# 15_eMMC_FLASH.net
KiCad netlist of a schematic drawn in Altium Designer
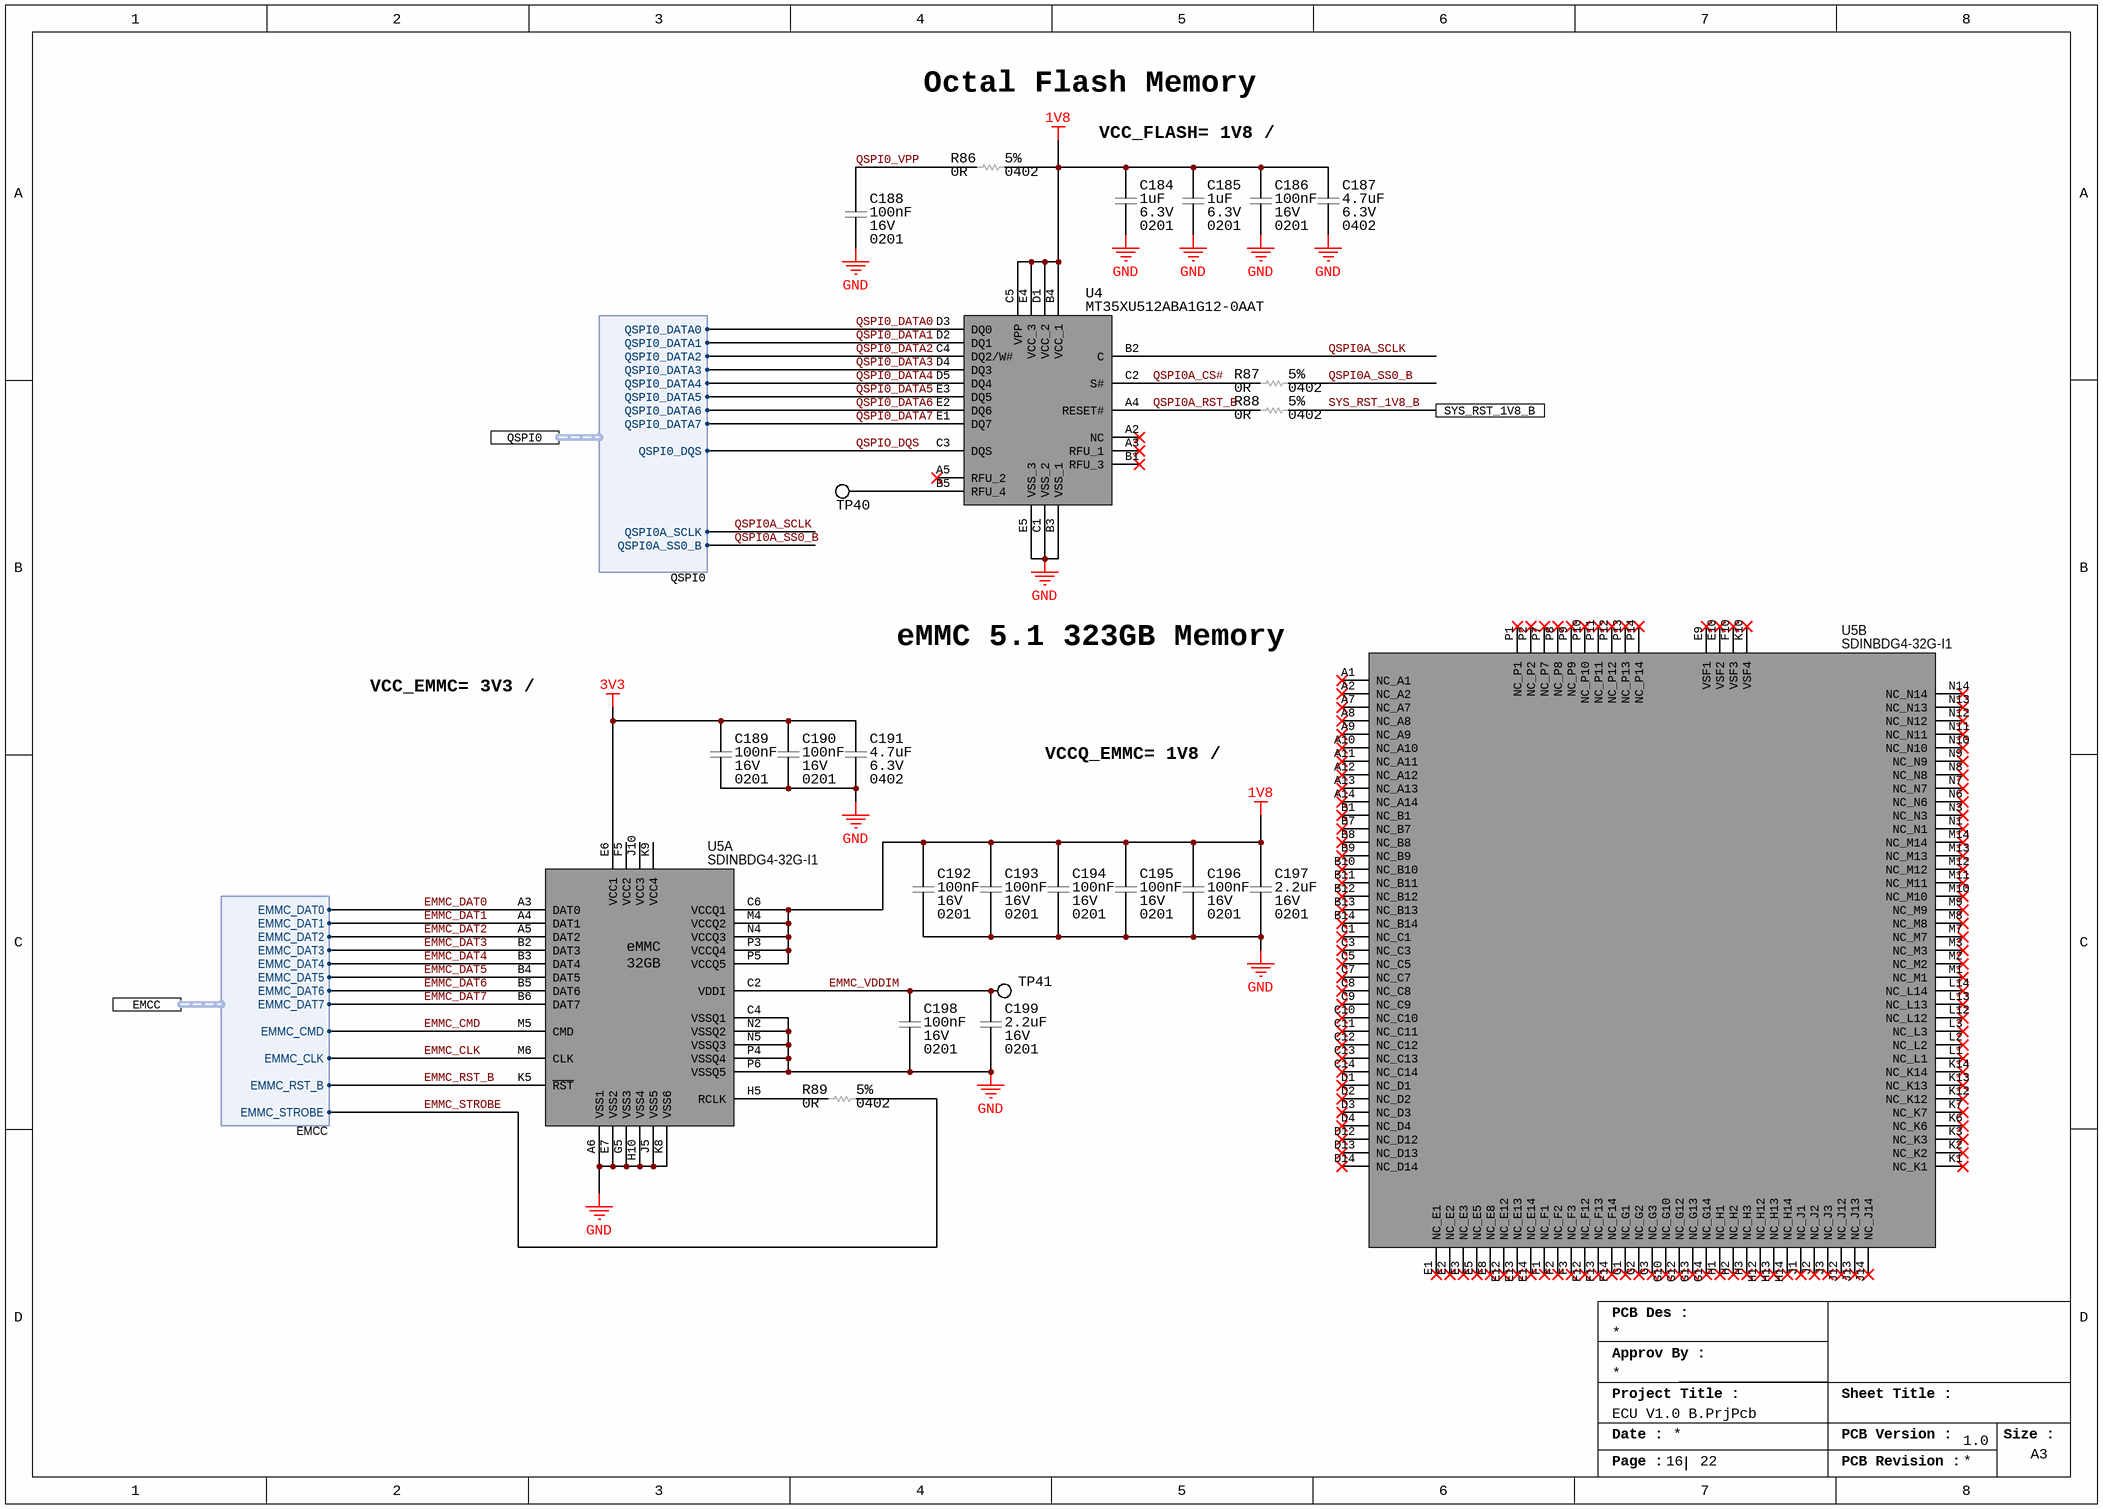
[diagram p0: 15_eMMC_FLASH.SchDoc]

(export (version "E")
  (design (tool "Eeschema 10.0.6"))
  (components
    (comp (ref "C184")
      (value "02016D105MAT2A")
      (footprint "CAP_0201_CAPC0603X03N")
      (description "0201 1 uF 6.3 V ±20 % Tolerance X5R Surface Mount Multilayer Ceramic Capacitor")
      (fields
        (field (name "MANUFACTURER") "Kyocera AVX")
        (field (name "TOLERANCE") "20%")
        (field (name "VOLTAGE RATING (DC)") "6.3V")
        (field (name "CAPACITANCE") "1uF")
        (field (name "CASE/PACKAGE") "0201")
      )
      (libsource (lib "Electronic Devices_LIB") (part "CAP_1UF_6.3V_X5R_0201"))
    )
    (comp (ref "C185")
      (value "02016D105MAT2A")
      (footprint "CAP_0201_CAPC0603X03N")
      (description "0201 1 uF 6.3 V ±20 % Tolerance X5R Surface Mount Multilayer Ceramic Capacitor")
      (fields
        (field (name "MANUFACTURER") "Kyocera AVX")
        (field (name "TOLERANCE") "20%")
        (field (name "VOLTAGE RATING (DC)") "6.3V")
        (field (name "CAPACITANCE") "1uF")
        (field (name "CASE/PACKAGE") "0201")
      )
      (libsource (lib "Electronic Devices_LIB") (part "CAP_1UF_6.3V_X5R_0201"))
    )
    (comp (ref "C186")
      (value "GRM033C71C104KE14D")
      (footprint "CAP_0201_CAPC0603X03N")
      (description "Multilayer Ceramic Capacitor, 0.1 uF, 16 V, ± 10%, X7S, 0201 [0603 Metric]")
      (fields
        (field (name "MANUFACTURER") "Murata")
        (field (name "TOLERANCE") "10%")
        (field (name "VOLTAGE RATING") "16V")
        (field (name "CAPACITANCE") "100nF")
        (field (name "CASE/PACKAGE") "0201")
      )
      (libsource (lib "Electronic Devices_LIB") (part "CAP_100nF_16V_X7S_0201"))
    )
    (comp (ref "C187")
      (value "C1005X5R0J475M050BC")
      (footprint "CAP_0402_CAPC1005X05N")
      (description "Multilayer Ceramic Capacitor, 4.7 uF, 6.3 V, ± 20%, X5R, 0402 [1005 Metric]")
      (fields
        (field (name "MANUFACTURER") "TDK")
        (field (name "TOLERANCE") "20%")
        (field (name "CAPACITANCE") "4.7uF")
        (field (name "VOLTAGE RATING") "6.3V")
        (field (name "CASE/PACKAGE") "0402")
      )
      (libsource (lib "Electronic Devices_LIB") (part "CAP_4.7UF_6.3V_X5R_0402"))
    )
    (comp (ref "C188")
      (value "GRM033C71C104KE14D")
      (footprint "CAP_0201_CAPC0603X03N")
      (description "Multilayer Ceramic Capacitor, 0.1 uF, 16 V, ± 10%, X7S, 0201 [0603 Metric]")
      (fields
        (field (name "MANUFACTURER") "Murata")
        (field (name "TOLERANCE") "10%")
        (field (name "VOLTAGE RATING") "16V")
        (field (name "CAPACITANCE") "100nF")
        (field (name "CASE/PACKAGE") "0201")
      )
      (libsource (lib "Electronic Devices_LIB") (part "CAP_100nF_16V_X7S_0201"))
    )
    (comp (ref "C189")
      (value "GRM033C71C104KE14D")
      (footprint "CAP_0201_CAPC0603X03N")
      (description "Multilayer Ceramic Capacitor, 0.1 uF, 16 V, ± 10%, X7S, 0201 [0603 Metric]")
      (fields
        (field (name "MANUFACTURER") "Murata")
        (field (name "TOLERANCE") "10%")
        (field (name "VOLTAGE RATING") "16V")
        (field (name "CAPACITANCE") "100nF")
        (field (name "CASE/PACKAGE") "0201")
      )
      (libsource (lib "Electronic Devices_LIB") (part "CAP_100nF_16V_X7S_0201"))
    )
    (comp (ref "C190")
      (value "GRM033C71C104KE14D")
      (footprint "CAP_0201_CAPC0603X03N")
      (description "Multilayer Ceramic Capacitor, 0.1 uF, 16 V, ± 10%, X7S, 0201 [0603 Metric]")
      (fields
        (field (name "MANUFACTURER") "Murata")
        (field (name "TOLERANCE") "10%")
        (field (name "VOLTAGE RATING") "16V")
        (field (name "CAPACITANCE") "100nF")
        (field (name "CASE/PACKAGE") "0201")
      )
      (libsource (lib "Electronic Devices_LIB") (part "CAP_100nF_16V_X7S_0201"))
    )
    (comp (ref "C191")
      (value "C1005X5R0J475M050BC")
      (footprint "CAP_0402_CAPC1005X05N")
      (description "Multilayer Ceramic Capacitor, 4.7 uF, 6.3 V, ± 20%, X5R, 0402 [1005 Metric]")
      (fields
        (field (name "MANUFACTURER") "TDK")
        (field (name "TOLERANCE") "20%")
        (field (name "CAPACITANCE") "4.7uF")
        (field (name "VOLTAGE RATING") "6.3V")
        (field (name "CASE/PACKAGE") "0402")
      )
      (libsource (lib "Electronic Devices_LIB") (part "CAP_4.7UF_6.3V_X5R_0402"))
    )
    (comp (ref "C192")
      (value "GRM033C71C104KE14D")
      (footprint "CAP_0201_CAPC0603X03N")
      (description "Multilayer Ceramic Capacitor, 0.1 uF, 16 V, ± 10%, X7S, 0201 [0603 Metric]")
      (fields
        (field (name "MANUFACTURER") "Murata")
        (field (name "TOLERANCE") "10%")
        (field (name "VOLTAGE RATING") "16V")
        (field (name "CAPACITANCE") "100nF")
        (field (name "CASE/PACKAGE") "0201")
      )
      (libsource (lib "Electronic Devices_LIB") (part "CAP_100nF_16V_X7S_0201"))
    )
    (comp (ref "C193")
      (value "GRM033C71C104KE14D")
      (footprint "CAP_0201_CAPC0603X03N")
      (description "Multilayer Ceramic Capacitor, 0.1 uF, 16 V, ± 10%, X7S, 0201 [0603 Metric]")
      (fields
        (field (name "MANUFACTURER") "Murata")
        (field (name "TOLERANCE") "10%")
        (field (name "VOLTAGE RATING") "16V")
        (field (name "CAPACITANCE") "100nF")
        (field (name "CASE/PACKAGE") "0201")
      )
      (libsource (lib "Electronic Devices_LIB") (part "CAP_100nF_16V_X7S_0201"))
    )
    (comp (ref "C194")
      (value "GRM033C71C104KE14D")
      (footprint "CAP_0201_CAPC0603X03N")
      (description "Multilayer Ceramic Capacitor, 0.1 uF, 16 V, ± 10%, X7S, 0201 [0603 Metric]")
      (fields
        (field (name "MANUFACTURER") "Murata")
        (field (name "TOLERANCE") "10%")
        (field (name "VOLTAGE RATING") "16V")
        (field (name "CAPACITANCE") "100nF")
        (field (name "CASE/PACKAGE") "0201")
      )
      (libsource (lib "Electronic Devices_LIB") (part "CAP_100nF_16V_X7S_0201"))
    )
    (comp (ref "C195")
      (value "GRM033C71C104KE14D")
      (footprint "CAP_0201_CAPC0603X03N")
      (description "Multilayer Ceramic Capacitor, 0.1 uF, 16 V, ± 10%, X7S, 0201 [0603 Metric]")
      (fields
        (field (name "MANUFACTURER") "Murata")
        (field (name "TOLERANCE") "10%")
        (field (name "VOLTAGE RATING") "16V")
        (field (name "CAPACITANCE") "100nF")
        (field (name "CASE/PACKAGE") "0201")
      )
      (libsource (lib "Electronic Devices_LIB") (part "CAP_100nF_16V_X7S_0201"))
    )
    (comp (ref "C196")
      (value "GRM033C71C104KE14D")
      (footprint "CAP_0201_CAPC0603X03N")
      (description "Multilayer Ceramic Capacitor, 0.1 uF, 16 V, ± 10%, X7S, 0201 [0603 Metric]")
      (fields
        (field (name "MANUFACTURER") "Murata")
        (field (name "TOLERANCE") "10%")
        (field (name "VOLTAGE RATING") "16V")
        (field (name "CAPACITANCE") "100nF")
        (field (name "CASE/PACKAGE") "0201")
      )
      (libsource (lib "Electronic Devices_LIB") (part "CAP_100nF_16V_X7S_0201"))
    )
    (comp (ref "C197")
      (value "GRM035R61C225ME01D")
      (footprint "CAP_0201_CAPC0603X03N")
      (description "General Up to 85C Reflow soldering")
      (fields
        (field (name "MANUFACTURER") "Murata")
        (field (name "TOLERANCE") "20%")
        (field (name "CAPACITANCE") "2.2uF")
        (field (name "VOLTAGE RATING") "16V")
        (field (name "CASE/PACKAGE") "0201")
      )
      (libsource (lib "Electronic Devices_LIB") (part "CAP_2.2uF_16V_X5R_0201"))
    )
    (comp (ref "C198")
      (value "GRM033C71C104KE14D")
      (footprint "CAP_0201_CAPC0603X03N")
      (description "Multilayer Ceramic Capacitor, 0.1 uF, 16 V, ± 10%, X7S, 0201 [0603 Metric]")
      (fields
        (field (name "MANUFACTURER") "Murata")
        (field (name "TOLERANCE") "10%")
        (field (name "VOLTAGE RATING") "16V")
        (field (name "CAPACITANCE") "100nF")
        (field (name "CASE/PACKAGE") "0201")
      )
      (libsource (lib "Electronic Devices_LIB") (part "CAP_100nF_16V_X7S_0201"))
    )
    (comp (ref "C199")
      (value "GRM035R61C225ME01D")
      (footprint "CAP_0201_CAPC0603X03N")
      (description "General Up to 85C Reflow soldering")
      (fields
        (field (name "MANUFACTURER") "Murata")
        (field (name "TOLERANCE") "20%")
        (field (name "CAPACITANCE") "2.2uF")
        (field (name "VOLTAGE RATING") "16V")
        (field (name "CASE/PACKAGE") "0201")
      )
      (libsource (lib "Electronic Devices_LIB") (part "CAP_2.2uF_16V_X5R_0201"))
    )
    (comp (ref "R86")
      (value "ERJ-2GE0R00X")
      (footprint "RES_0402_RESC1005X04N")
      (description "SMD Chip Resistor, Jumper, 0 ohm, 100 mW, 0402 [1005 Metric], Thick Film, General Purpose")
      (fields
        (field (name "MANUFACTURER") "Panasonic")
        (field (name "CASE CODE (IMPERIAL)") "0402")
        (field (name "TOLERANCE") "5%")
        (field (name "RESISTANCE") "0R")
      )
      (libsource (lib "Electronic Devices_LIB") (part "RES_0R_5%_100mW_0402"))
    )
    (comp (ref "R87")
      (value "ERJ-2GE0R00X")
      (footprint "RES_0402_RESC1005X04N")
      (description "SMD Chip Resistor, Jumper, 0 ohm, 100 mW, 0402 [1005 Metric], Thick Film, General Purpose")
      (fields
        (field (name "MANUFACTURER") "Panasonic")
        (field (name "CASE CODE (IMPERIAL)") "0402")
        (field (name "TOLERANCE") "5%")
        (field (name "RESISTANCE") "0R")
      )
      (libsource (lib "Electronic Devices_LIB") (part "RES_0R_5%_100mW_0402"))
    )
    (comp (ref "R88")
      (value "ERJ-2GE0R00X")
      (footprint "RES_0402_RESC1005X04N")
      (description "SMD Chip Resistor, Jumper, 0 ohm, 100 mW, 0402 [1005 Metric], Thick Film, General Purpose")
      (fields
        (field (name "MANUFACTURER") "Panasonic")
        (field (name "CASE CODE (IMPERIAL)") "0402")
        (field (name "TOLERANCE") "5%")
        (field (name "RESISTANCE") "0R")
      )
      (libsource (lib "Electronic Devices_LIB") (part "RES_0R_5%_100mW_0402"))
    )
    (comp (ref "R89")
      (value "ERJ-2GE0R00X")
      (footprint "RES_0402_RESC1005X04N")
      (description "SMD Chip Resistor, Jumper, 0 ohm, 100 mW, 0402 [1005 Metric], Thick Film, General Purpose")
      (fields
        (field (name "MANUFACTURER") "Panasonic")
        (field (name "CASE CODE (IMPERIAL)") "0402")
        (field (name "TOLERANCE") "5%")
        (field (name "RESISTANCE") "0R")
      )
      (libsource (lib "Electronic Devices_LIB") (part "RES_0R_5%_100mW_0402"))
    )
    (comp (ref "TP40")
      (value "NO COMPONENT")
      (footprint "TP_PAD_0.5MM_SMD_ROUND")
      (description "Test Point, SMD pad, round, 1.5mm, 1.6mm, 3mm diameter")
      (libsource (lib "Electronic Devices_LIB") (part "TP_PAD_SMD_SMALL"))
    )
    (comp (ref "TP41")
      (value "NO COMPONENT")
      (footprint "TP_PAD_0.5MM_SMD_ROUND")
      (description "Test Point, SMD pad, round, 1.5mm, 1.6mm, 3mm diameter")
      (libsource (lib "Electronic Devices_LIB") (part "TP_PAD_SMD_SMALL"))
    )
    (comp (ref "U4")
      (value "MT35XU512ABA1G12-0AAT")
      (footprint "BGA24C100P5X5_600X800X120")
      (description "NOR Flash, NOR Flash for Automotive, 512Mb, 1.7V-2.0V, 200 MHz, 24-ball T-PBGA, RoHS")
      (fields (field (name "MANUFACTURER") "Micron Technology"))
      (libsource (lib "Electronic Devices_LIB") (part "IC_MEMORY_FLASH_512Mb_MT35XU512ABA1G12-0AAT"))
    )
    (comp (ref "U5")
      (value "SDINBDG4-32G-I1")
      (footprint "IC_MEMORY_eMMC")
      (description "Inand 7250 32GB Industrial Wide Temp -25C+85C EMMC5.1 HS400")
      (fields (field (name "MANUFACTURER") "SanDisk"))
      (libsource (lib "Electronic Devices_LIB") (part "IC_MEMORY_eMMC_SDINBDG4-32G-I1"))
    )
  )
  (nets
    (net (code "3") (name "/EMMC_CLK") (class "Default")
      (node (ref "U5") (pin "M6") (pinfunction "CLK_M6") (pintype "passive"))
    )
    (net (code "4") (name "/EMMC_CMD") (class "Default")
      (node (ref "U5") (pin "M5") (pinfunction "CMD_M5") (pintype "passive"))
    )
    (net (code "5") (name "/EMMC_DAT0") (class "Default")
      (node (ref "U5") (pin "A3") (pinfunction "DAT0_A3") (pintype "passive"))
    )
    (net (code "6") (name "/EMMC_DAT1") (class "Default")
      (node (ref "U5") (pin "A4") (pinfunction "DAT1_A4") (pintype "passive"))
    )
    (net (code "7") (name "/EMMC_DAT2") (class "Default")
      (node (ref "U5") (pin "A5") (pinfunction "DAT2_A5") (pintype "passive"))
    )
    (net (code "8") (name "/EMMC_DAT3") (class "Default")
      (node (ref "U5") (pin "B2") (pinfunction "DAT3_B2") (pintype "passive"))
    )
    (net (code "9") (name "/EMMC_DAT4") (class "Default")
      (node (ref "U5") (pin "B3") (pinfunction "DAT4_B3") (pintype "passive"))
    )
    (net (code "10") (name "/EMMC_DAT5") (class "Default")
      (node (ref "U5") (pin "B4") (pinfunction "DAT5_B4") (pintype "passive"))
    )
    (net (code "11") (name "/EMMC_DAT6") (class "Default")
      (node (ref "U5") (pin "B5") (pinfunction "DAT6_B5") (pintype "passive"))
    )
    (net (code "12") (name "/EMMC_DAT7") (class "Default")
      (node (ref "U5") (pin "B6") (pinfunction "DAT7_B6") (pintype "passive"))
    )
    (net (code "13") (name "/EMMC_RST_B") (class "Default")
      (node (ref "U5") (pin "K5") (pinfunction "~{RST}_K5") (pintype "passive"))
    )
    (net (code "14") (name "/EMMC_STROBE") (class "Default")
      (node (ref "R89") (pin "2") (pinfunction "2_2") (pintype "passive"))
    )
    (net (code "15") (name "/EMMC_VDDIM") (class "Default")
      (node (ref "C198") (pin "2") (pinfunction "2_2") (pintype "passive"))
      (node (ref "C199") (pin "2") (pinfunction "2_2") (pintype "passive"))
      (node (ref "TP41") (pin "1") (pinfunction "1_1") (pintype "passive"))
      (node (ref "U5") (pin "C2") (pinfunction "VDDI_C2") (pintype "power_in"))
    )
    (net (code "16") (name "/QSPI0A_CS#") (class "Default")
      (node (ref "R87") (pin "1") (pinfunction "1_1") (pintype "passive"))
      (node (ref "U4") (pin "C2") (pinfunction "S#_C2") (pintype "passive"))
    )
    (net (code "17") (name "/QSPI0A_RST_B") (class "Default")
      (node (ref "R88") (pin "1") (pinfunction "1_1") (pintype "passive"))
      (node (ref "U4") (pin "A4") (pinfunction "RESET#_A4") (pintype "passive"))
    )
    (net (code "18") (name "/QSPI0A_SCLK") (class "Default")
      (node (ref "U4") (pin "B2") (pinfunction "C_B2") (pintype "passive"))
    )
    (net (code "19") (name "/QSPI0A_SS0_B") (class "Default")
      (node (ref "R87") (pin "2") (pinfunction "2_2") (pintype "passive"))
    )
    (net (code "20") (name "/QSPI0_DATA0") (class "Default")
      (node (ref "U4") (pin "D3") (pinfunction "DQ0_D3") (pintype "passive"))
    )
    (net (code "21") (name "/QSPI0_DATA1") (class "Default")
      (node (ref "U4") (pin "D2") (pinfunction "DQ1_D2") (pintype "passive"))
    )
    (net (code "22") (name "/QSPI0_DATA2") (class "Default")
      (node (ref "U4") (pin "C4") (pinfunction "DQ2/W#_C4") (pintype "passive"))
    )
    (net (code "23") (name "/QSPI0_DATA3") (class "Default")
      (node (ref "U4") (pin "D4") (pinfunction "DQ3_D4") (pintype "passive"))
    )
    (net (code "24") (name "/QSPI0_DATA4") (class "Default")
      (node (ref "U4") (pin "D5") (pinfunction "DQ4_D5") (pintype "passive"))
    )
    (net (code "25") (name "/QSPI0_DATA5") (class "Default")
      (node (ref "U4") (pin "E3") (pinfunction "DQ5_E3") (pintype "passive"))
    )
    (net (code "26") (name "/QSPI0_DATA6") (class "Default")
      (node (ref "U4") (pin "E2") (pinfunction "DQ6_E2") (pintype "passive"))
    )
    (net (code "27") (name "/QSPI0_DATA7") (class "Default")
      (node (ref "U4") (pin "E1") (pinfunction "DQ7_E1") (pintype "passive"))
    )
    (net (code "28") (name "/QSPI0_VPP") (class "Default")
      (node (ref "C188") (pin "2") (pinfunction "2_2") (pintype "passive"))
      (node (ref "R86") (pin "1") (pinfunction "1_1") (pintype "passive"))
    )
    (net (code "29") (name "/QSPIO_DQS") (class "Default")
      (node (ref "U4") (pin "C3") (pinfunction "DQS_C3") (pintype "passive"))
    )
    (net (code "30") (name "/SYS_RST_1V8_B") (class "Default")
      (node (ref "R88") (pin "2") (pinfunction "2_2") (pintype "passive"))
    )
    (net (code "33") (name "1V8") (class "Default")
      (node (ref "C184") (pin "2") (pinfunction "2_2") (pintype "passive"))
      (node (ref "C185") (pin "2") (pinfunction "2_2") (pintype "passive"))
      (node (ref "C186") (pin "2") (pinfunction "2_2") (pintype "passive"))
      (node (ref "C187") (pin "2") (pinfunction "2_2") (pintype "passive"))
      (node (ref "C192") (pin "2") (pinfunction "2_2") (pintype "passive"))
      (node (ref "C193") (pin "2") (pinfunction "2_2") (pintype "passive"))
      (node (ref "C194") (pin "2") (pinfunction "2_2") (pintype "passive"))
      (node (ref "C195") (pin "2") (pinfunction "2_2") (pintype "passive"))
      (node (ref "C196") (pin "2") (pinfunction "2_2") (pintype "passive"))
      (node (ref "C197") (pin "2") (pinfunction "2_2") (pintype "passive"))
      (node (ref "R86") (pin "2") (pinfunction "2_2") (pintype "passive"))
      (node (ref "U4") (pin "B4") (pinfunction "VCC_1_B4") (pintype "passive"))
      (node (ref "U4") (pin "C5") (pinfunction "VPP_C5") (pintype "passive"))
      (node (ref "U4") (pin "D1") (pinfunction "VCC_2_D1") (pintype "passive"))
      (node (ref "U4") (pin "E4") (pinfunction "VCC_3_E4") (pintype "passive"))
      (node (ref "U5") (pin "C6") (pinfunction "VCCQ1_C6") (pintype "power_in"))
      (node (ref "U5") (pin "M4") (pinfunction "VCCQ2_M4") (pintype "power_in"))
      (node (ref "U5") (pin "N4") (pinfunction "VCCQ3_N4") (pintype "power_in"))
      (node (ref "U5") (pin "P3") (pinfunction "VCCQ4_P3") (pintype "power_in"))
      (node (ref "U5") (pin "P5") (pinfunction "VCCQ5_P5") (pintype "power_in"))
    )
    (net (code "34") (name "3V3") (class "Default")
      (node (ref "C189") (pin "2") (pinfunction "2_2") (pintype "passive"))
      (node (ref "C190") (pin "2") (pinfunction "2_2") (pintype "passive"))
      (node (ref "C191") (pin "2") (pinfunction "2_2") (pintype "passive"))
      (node (ref "U5") (pin "E6") (pinfunction "VCC1_E6") (pintype "power_in"))
    )
    (net (code "35") (name "GND") (class "Default")
      (node (ref "C184") (pin "1") (pinfunction "1_1") (pintype "passive"))
      (node (ref "C185") (pin "1") (pinfunction "1_1") (pintype "passive"))
      (node (ref "C186") (pin "1") (pinfunction "1_1") (pintype "passive"))
      (node (ref "C187") (pin "1") (pinfunction "1_1") (pintype "passive"))
      (node (ref "C188") (pin "1") (pinfunction "1_1") (pintype "passive"))
      (node (ref "C189") (pin "1") (pinfunction "1_1") (pintype "passive"))
      (node (ref "C190") (pin "1") (pinfunction "1_1") (pintype "passive"))
      (node (ref "C191") (pin "1") (pinfunction "1_1") (pintype "passive"))
      (node (ref "C192") (pin "1") (pinfunction "1_1") (pintype "passive"))
      (node (ref "C193") (pin "1") (pinfunction "1_1") (pintype "passive"))
      (node (ref "C194") (pin "1") (pinfunction "1_1") (pintype "passive"))
      (node (ref "C195") (pin "1") (pinfunction "1_1") (pintype "passive"))
      (node (ref "C196") (pin "1") (pinfunction "1_1") (pintype "passive"))
      (node (ref "C197") (pin "1") (pinfunction "1_1") (pintype "passive"))
      (node (ref "C198") (pin "1") (pinfunction "1_1") (pintype "passive"))
      (node (ref "C199") (pin "1") (pinfunction "1_1") (pintype "passive"))
      (node (ref "U4") (pin "B3") (pinfunction "VSS_1_B3") (pintype "passive"))
      (node (ref "U4") (pin "C1") (pinfunction "VSS_2_C1") (pintype "passive"))
      (node (ref "U4") (pin "E5") (pinfunction "VSS_3_E5") (pintype "passive"))
      (node (ref "U5") (pin "A6") (pinfunction "VSS1_A6") (pintype "power_in"))
      (node (ref "U5") (pin "C4") (pinfunction "VSSQ1_C4") (pintype "power_in"))
      (node (ref "U5") (pin "E7") (pinfunction "VSS2_E7") (pintype "power_in"))
      (node (ref "U5") (pin "G5") (pinfunction "VSS3_G5") (pintype "power_in"))
      (node (ref "U5") (pin "H10") (pinfunction "VSS4_H10") (pintype "power_in"))
      (node (ref "U5") (pin "J5") (pinfunction "VSS5_J5") (pintype "power_in"))
      (node (ref "U5") (pin "K8") (pinfunction "VSS6_K8") (pintype "power_in"))
      (node (ref "U5") (pin "N2") (pinfunction "VSSQ2_N2") (pintype "power_in"))
      (node (ref "U5") (pin "N5") (pinfunction "VSSQ3_N5") (pintype "power_in"))
      (node (ref "U5") (pin "P4") (pinfunction "VSSQ4_P4") (pintype "power_in"))
      (node (ref "U5") (pin "P6") (pinfunction "VSSQ5_P6") (pintype "power_in"))
    )
    (net (code "36") (name "Net-(U4-RFU_4)") (class "Default")
      (node (ref "TP40") (pin "1") (pinfunction "1_1") (pintype "passive"))
      (node (ref "U4") (pin "B5") (pinfunction "RFU_4_B5") (pintype "passive"))
    )
    (net (code "37") (name "Net-(U5A-RCLK)") (class "Default")
      (node (ref "R89") (pin "1") (pinfunction "1_1") (pintype "passive"))
      (node (ref "U5") (pin "H5") (pinfunction "RCLK_H5") (pintype "passive"))
    )
    (net (code "38") (name "unconnected-(U4-NC-PadA2)") (class "Default")
      (node (ref "U4") (pin "A2") (pinfunction "NC_A2") (pintype "passive+no_connect"))
    )
    (net (code "39") (name "unconnected-(U4-RFU_1-PadA3)") (class "Default")
      (node (ref "U4") (pin "A3") (pinfunction "RFU_1_A3") (pintype "passive+no_connect"))
    )
    (net (code "40") (name "unconnected-(U4-RFU_2-PadA5)") (class "Default")
      (node (ref "U4") (pin "A5") (pinfunction "RFU_2_A5") (pintype "passive+no_connect"))
    )
    (net (code "41") (name "unconnected-(U4-RFU_3-PadB1)") (class "Default")
      (node (ref "U4") (pin "B1") (pinfunction "RFU_3_B1") (pintype "passive+no_connect"))
    )
    (net (code "42") (name "unconnected-(U5A-VCC2-PadF5)") (class "Default")
      (node (ref "U5") (pin "F5") (pinfunction "VCC2_F5") (pintype "power_in"))
    )
    (net (code "43") (name "unconnected-(U5A-VCC3-PadJ10)") (class "Default")
      (node (ref "U5") (pin "J10") (pinfunction "VCC3_J10") (pintype "power_in"))
    )
    (net (code "44") (name "unconnected-(U5A-VCC4-PadK9)") (class "Default")
      (node (ref "U5") (pin "K9") (pinfunction "VCC4_K9") (pintype "power_in"))
    )
    (net (code "45") (name "unconnected-(U5B-NC_A1-PadA1)") (class "Default")
      (node (ref "U5") (pin "A1") (pinfunction "NC_A1_A1") (pintype "passive+no_connect"))
    )
    (net (code "46") (name "unconnected-(U5B-NC_A2-PadA2)") (class "Default")
      (node (ref "U5") (pin "A2") (pinfunction "NC_A2_A2") (pintype "passive+no_connect"))
    )
    (net (code "47") (name "unconnected-(U5B-NC_A7-PadA7)") (class "Default")
      (node (ref "U5") (pin "A7") (pinfunction "NC_A7_A7") (pintype "passive+no_connect"))
    )
    (net (code "48") (name "unconnected-(U5B-NC_A8-PadA8)") (class "Default")
      (node (ref "U5") (pin "A8") (pinfunction "NC_A8_A8") (pintype "passive+no_connect"))
    )
    (net (code "49") (name "unconnected-(U5B-NC_A9-PadA9)") (class "Default")
      (node (ref "U5") (pin "A9") (pinfunction "NC_A9_A9") (pintype "passive+no_connect"))
    )
    (net (code "50") (name "unconnected-(U5B-NC_A10-PadA10)") (class "Default")
      (node (ref "U5") (pin "A10") (pinfunction "NC_A10_A10") (pintype "passive+no_connect"))
    )
    (net (code "51") (name "unconnected-(U5B-NC_A11-PadA11)") (class "Default")
      (node (ref "U5") (pin "A11") (pinfunction "NC_A11_A11") (pintype "passive+no_connect"))
    )
    (net (code "52") (name "unconnected-(U5B-NC_A12-PadA12)") (class "Default")
      (node (ref "U5") (pin "A12") (pinfunction "NC_A12_A12") (pintype "passive+no_connect"))
    )
    (net (code "53") (name "unconnected-(U5B-NC_A13-PadA13)") (class "Default")
      (node (ref "U5") (pin "A13") (pinfunction "NC_A13_A13") (pintype "passive+no_connect"))
    )
    (net (code "54") (name "unconnected-(U5B-NC_A14-PadA14)") (class "Default")
      (node (ref "U5") (pin "A14") (pinfunction "NC_A14_A14") (pintype "passive+no_connect"))
    )
    (net (code "55") (name "unconnected-(U5B-NC_B1-PadB1)") (class "Default")
      (node (ref "U5") (pin "B1") (pinfunction "NC_B1_B1") (pintype "passive+no_connect"))
    )
    (net (code "56") (name "unconnected-(U5B-NC_B7-PadB7)") (class "Default")
      (node (ref "U5") (pin "B7") (pinfunction "NC_B7_B7") (pintype "passive+no_connect"))
    )
    (net (code "57") (name "unconnected-(U5B-NC_B8-PadB8)") (class "Default")
      (node (ref "U5") (pin "B8") (pinfunction "NC_B8_B8") (pintype "passive+no_connect"))
    )
    (net (code "58") (name "unconnected-(U5B-NC_B9-PadB9)") (class "Default")
      (node (ref "U5") (pin "B9") (pinfunction "NC_B9_B9") (pintype "passive+no_connect"))
    )
    (net (code "59") (name "unconnected-(U5B-NC_B10-PadB10)") (class "Default")
      (node (ref "U5") (pin "B10") (pinfunction "NC_B10_B10") (pintype "passive+no_connect"))
    )
    (net (code "60") (name "unconnected-(U5B-NC_B11-PadB11)") (class "Default")
      (node (ref "U5") (pin "B11") (pinfunction "NC_B11_B11") (pintype "passive+no_connect"))
    )
    (net (code "61") (name "unconnected-(U5B-NC_B12-PadB12)") (class "Default")
      (node (ref "U5") (pin "B12") (pinfunction "NC_B12_B12") (pintype "passive+no_connect"))
    )
    (net (code "62") (name "unconnected-(U5B-NC_B13-PadB13)") (class "Default")
      (node (ref "U5") (pin "B13") (pinfunction "NC_B13_B13") (pintype "passive+no_connect"))
    )
    (net (code "63") (name "unconnected-(U5B-NC_B14-PadB14)") (class "Default")
      (node (ref "U5") (pin "B14") (pinfunction "NC_B14_B14") (pintype "passive+no_connect"))
    )
    (net (code "64") (name "unconnected-(U5B-NC_C1-PadC1)") (class "Default")
      (node (ref "U5") (pin "C1") (pinfunction "NC_C1_C1") (pintype "passive+no_connect"))
    )
    (net (code "65") (name "unconnected-(U5B-NC_C3-PadC3)") (class "Default")
      (node (ref "U5") (pin "C3") (pinfunction "NC_C3_C3") (pintype "passive+no_connect"))
    )
    (net (code "66") (name "unconnected-(U5B-NC_C5-PadC5)") (class "Default")
      (node (ref "U5") (pin "C5") (pinfunction "NC_C5_C5") (pintype "passive+no_connect"))
    )
    (net (code "67") (name "unconnected-(U5B-NC_C7-PadC7)") (class "Default")
      (node (ref "U5") (pin "C7") (pinfunction "NC_C7_C7") (pintype "passive+no_connect"))
    )
    (net (code "68") (name "unconnected-(U5B-NC_C8-PadC8)") (class "Default")
      (node (ref "U5") (pin "C8") (pinfunction "NC_C8_C8") (pintype "passive+no_connect"))
    )
    (net (code "69") (name "unconnected-(U5B-NC_C9-PadC9)") (class "Default")
      (node (ref "U5") (pin "C9") (pinfunction "NC_C9_C9") (pintype "passive+no_connect"))
    )
    (net (code "70") (name "unconnected-(U5B-NC_C10-PadC10)") (class "Default")
      (node (ref "U5") (pin "C10") (pinfunction "NC_C10_C10") (pintype "passive+no_connect"))
    )
    (net (code "71") (name "unconnected-(U5B-NC_C11-PadC11)") (class "Default")
      (node (ref "U5") (pin "C11") (pinfunction "NC_C11_C11") (pintype "passive+no_connect"))
    )
    (net (code "72") (name "unconnected-(U5B-NC_C12-PadC12)") (class "Default")
      (node (ref "U5") (pin "C12") (pinfunction "NC_C12_C12") (pintype "passive+no_connect"))
    )
    (net (code "73") (name "unconnected-(U5B-NC_C13-PadC13)") (class "Default")
      (node (ref "U5") (pin "C13") (pinfunction "NC_C13_C13") (pintype "passive+no_connect"))
    )
    (net (code "74") (name "unconnected-(U5B-NC_C14-PadC14)") (class "Default")
      (node (ref "U5") (pin "C14") (pinfunction "NC_C14_C14") (pintype "passive+no_connect"))
    )
    (net (code "75") (name "unconnected-(U5B-NC_D1-PadD1)") (class "Default")
      (node (ref "U5") (pin "D1") (pinfunction "NC_D1_D1") (pintype "passive+no_connect"))
    )
    (net (code "76") (name "unconnected-(U5B-NC_D2-PadD2)") (class "Default")
      (node (ref "U5") (pin "D2") (pinfunction "NC_D2_D2") (pintype "passive+no_connect"))
    )
    (net (code "77") (name "unconnected-(U5B-NC_D3-PadD3)") (class "Default")
      (node (ref "U5") (pin "D3") (pinfunction "NC_D3_D3") (pintype "passive+no_connect"))
    )
    (net (code "78") (name "unconnected-(U5B-NC_D4-PadD4)") (class "Default")
      (node (ref "U5") (pin "D4") (pinfunction "NC_D4_D4") (pintype "passive+no_connect"))
    )
    (net (code "79") (name "unconnected-(U5B-NC_D12-PadD12)") (class "Default")
      (node (ref "U5") (pin "D12") (pinfunction "NC_D12_D12") (pintype "passive+no_connect"))
    )
    (net (code "80") (name "unconnected-(U5B-NC_D13-PadD13)") (class "Default")
      (node (ref "U5") (pin "D13") (pinfunction "NC_D13_D13") (pintype "passive+no_connect"))
    )
    (net (code "81") (name "unconnected-(U5B-NC_D14-PadD14)") (class "Default")
      (node (ref "U5") (pin "D14") (pinfunction "NC_D14_D14") (pintype "passive+no_connect"))
    )
    (net (code "82") (name "unconnected-(U5B-NC_E1-PadE1)") (class "Default")
      (node (ref "U5") (pin "E1") (pinfunction "NC_E1_E1") (pintype "passive+no_connect"))
    )
    (net (code "83") (name "unconnected-(U5B-NC_E2-PadE2)") (class "Default")
      (node (ref "U5") (pin "E2") (pinfunction "NC_E2_E2") (pintype "passive+no_connect"))
    )
    (net (code "84") (name "unconnected-(U5B-NC_E3-PadE3)") (class "Default")
      (node (ref "U5") (pin "E3") (pinfunction "NC_E3_E3") (pintype "passive+no_connect"))
    )
    (net (code "85") (name "unconnected-(U5B-NC_E5-PadE5)") (class "Default")
      (node (ref "U5") (pin "E5") (pinfunction "NC_E5_E5") (pintype "passive+no_connect"))
    )
    (net (code "86") (name "unconnected-(U5B-NC_E8-PadE8)") (class "Default")
      (node (ref "U5") (pin "E8") (pinfunction "NC_E8_E8") (pintype "passive+no_connect"))
    )
    (net (code "87") (name "unconnected-(U5B-NC_E12-PadE12)") (class "Default")
      (node (ref "U5") (pin "E12") (pinfunction "NC_E12_E12") (pintype "passive+no_connect"))
    )
    (net (code "88") (name "unconnected-(U5B-NC_E13-PadE13)") (class "Default")
      (node (ref "U5") (pin "E13") (pinfunction "NC_E13_E13") (pintype "passive+no_connect"))
    )
    (net (code "89") (name "unconnected-(U5B-NC_E14-PadE14)") (class "Default")
      (node (ref "U5") (pin "E14") (pinfunction "NC_E14_E14") (pintype "passive+no_connect"))
    )
    (net (code "90") (name "unconnected-(U5B-NC_F1-PadF1)") (class "Default")
      (node (ref "U5") (pin "F1") (pinfunction "NC_F1_F1") (pintype "passive+no_connect"))
    )
    (net (code "91") (name "unconnected-(U5B-NC_F2-PadF2)") (class "Default")
      (node (ref "U5") (pin "F2") (pinfunction "NC_F2_F2") (pintype "passive+no_connect"))
    )
    (net (code "92") (name "unconnected-(U5B-NC_F3-PadF3)") (class "Default")
      (node (ref "U5") (pin "F3") (pinfunction "NC_F3_F3") (pintype "passive+no_connect"))
    )
    (net (code "93") (name "unconnected-(U5B-NC_F12-PadF12)") (class "Default")
      (node (ref "U5") (pin "F12") (pinfunction "NC_F12_F12") (pintype "passive+no_connect"))
    )
    (net (code "94") (name "unconnected-(U5B-NC_F13-PadF13)") (class "Default")
      (node (ref "U5") (pin "F13") (pinfunction "NC_F13_F13") (pintype "passive+no_connect"))
    )
    (net (code "95") (name "unconnected-(U5B-NC_F14-PadF14)") (class "Default")
      (node (ref "U5") (pin "F14") (pinfunction "NC_F14_F14") (pintype "passive+no_connect"))
    )
    (net (code "96") (name "unconnected-(U5B-NC_G1-PadG1)") (class "Default")
      (node (ref "U5") (pin "G1") (pinfunction "NC_G1_G1") (pintype "passive+no_connect"))
    )
    (net (code "97") (name "unconnected-(U5B-NC_G2-PadG2)") (class "Default")
      (node (ref "U5") (pin "G2") (pinfunction "NC_G2_G2") (pintype "passive+no_connect"))
    )
    (net (code "98") (name "unconnected-(U5B-NC_G3-PadG3)") (class "Default")
      (node (ref "U5") (pin "G3") (pinfunction "NC_G3_G3") (pintype "passive+no_connect"))
    )
    (net (code "99") (name "unconnected-(U5B-NC_G10-PadG10)") (class "Default")
      (node (ref "U5") (pin "G10") (pinfunction "NC_G10_G10") (pintype "passive+no_connect"))
    )
    (net (code "100") (name "unconnected-(U5B-NC_G12-PadG12)") (class "Default")
      (node (ref "U5") (pin "G12") (pinfunction "NC_G12_G12") (pintype "passive+no_connect"))
    )
    (net (code "101") (name "unconnected-(U5B-NC_G13-PadG13)") (class "Default")
      (node (ref "U5") (pin "G13") (pinfunction "NC_G13_G13") (pintype "passive+no_connect"))
    )
    (net (code "102") (name "unconnected-(U5B-NC_G14-PadG14)") (class "Default")
      (node (ref "U5") (pin "G14") (pinfunction "NC_G14_G14") (pintype "passive+no_connect"))
    )
    (net (code "103") (name "unconnected-(U5B-NC_H1-PadH1)") (class "Default")
      (node (ref "U5") (pin "H1") (pinfunction "NC_H1_H1") (pintype "passive+no_connect"))
    )
    (net (code "104") (name "unconnected-(U5B-NC_H2-PadH2)") (class "Default")
      (node (ref "U5") (pin "H2") (pinfunction "NC_H2_H2") (pintype "passive+no_connect"))
    )
    (net (code "105") (name "unconnected-(U5B-NC_H3-PadH3)") (class "Default")
      (node (ref "U5") (pin "H3") (pinfunction "NC_H3_H3") (pintype "passive+no_connect"))
    )
    (net (code "106") (name "unconnected-(U5B-NC_H12-PadH12)") (class "Default")
      (node (ref "U5") (pin "H12") (pinfunction "NC_H12_H12") (pintype "passive+no_connect"))
    )
    (net (code "107") (name "unconnected-(U5B-NC_H13-PadH13)") (class "Default")
      (node (ref "U5") (pin "H13") (pinfunction "NC_H13_H13") (pintype "passive+no_connect"))
    )
    (net (code "108") (name "unconnected-(U5B-NC_H14-PadH14)") (class "Default")
      (node (ref "U5") (pin "H14") (pinfunction "NC_H14_H14") (pintype "passive+no_connect"))
    )
    (net (code "109") (name "unconnected-(U5B-NC_J1-PadJ1)") (class "Default")
      (node (ref "U5") (pin "J1") (pinfunction "NC_J1_J1") (pintype "passive+no_connect"))
    )
    (net (code "110") (name "unconnected-(U5B-NC_J2-PadJ2)") (class "Default")
      (node (ref "U5") (pin "J2") (pinfunction "NC_J2_J2") (pintype "passive+no_connect"))
    )
    (net (code "111") (name "unconnected-(U5B-NC_J3-PadJ3)") (class "Default")
      (node (ref "U5") (pin "J3") (pinfunction "NC_J3_J3") (pintype "passive+no_connect"))
    )
    (net (code "112") (name "unconnected-(U5B-NC_J12-PadJ12)") (class "Default")
      (node (ref "U5") (pin "J12") (pinfunction "NC_J12_J12") (pintype "passive+no_connect"))
    )
    (net (code "113") (name "unconnected-(U5B-NC_J13-PadJ13)") (class "Default")
      (node (ref "U5") (pin "J13") (pinfunction "NC_J13_J13") (pintype "passive+no_connect"))
    )
    (net (code "114") (name "unconnected-(U5B-NC_J14-PadJ14)") (class "Default")
      (node (ref "U5") (pin "J14") (pinfunction "NC_J14_J14") (pintype "passive+no_connect"))
    )
    (net (code "115") (name "unconnected-(U5B-NC_K1-PadK1)") (class "Default")
      (node (ref "U5") (pin "K1") (pinfunction "NC_K1_K1") (pintype "passive+no_connect"))
    )
    (net (code "116") (name "unconnected-(U5B-NC_K2-PadK2)") (class "Default")
      (node (ref "U5") (pin "K2") (pinfunction "NC_K2_K2") (pintype "passive+no_connect"))
    )
    (net (code "117") (name "unconnected-(U5B-NC_K3-PadK3)") (class "Default")
      (node (ref "U5") (pin "K3") (pinfunction "NC_K3_K3") (pintype "passive+no_connect"))
    )
    (net (code "118") (name "unconnected-(U5B-NC_K6-PadK6)") (class "Default")
      (node (ref "U5") (pin "K6") (pinfunction "NC_K6_K6") (pintype "passive+no_connect"))
    )
    (net (code "119") (name "unconnected-(U5B-NC_K7-PadK7)") (class "Default")
      (node (ref "U5") (pin "K7") (pinfunction "NC_K7_K7") (pintype "passive+no_connect"))
    )
    (net (code "120") (name "unconnected-(U5B-NC_K12-PadK12)") (class "Default")
      (node (ref "U5") (pin "K12") (pinfunction "NC_K12_K12") (pintype "passive+no_connect"))
    )
    (net (code "121") (name "unconnected-(U5B-NC_K13-PadK13)") (class "Default")
      (node (ref "U5") (pin "K13") (pinfunction "NC_K13_K13") (pintype "passive+no_connect"))
    )
    (net (code "122") (name "unconnected-(U5B-NC_K14-PadK14)") (class "Default")
      (node (ref "U5") (pin "K14") (pinfunction "NC_K14_K14") (pintype "passive+no_connect"))
    )
    (net (code "123") (name "unconnected-(U5B-NC_L1-PadL1)") (class "Default")
      (node (ref "U5") (pin "L1") (pinfunction "NC_L1_L1") (pintype "passive+no_connect"))
    )
    (net (code "124") (name "unconnected-(U5B-NC_L2-PadL2)") (class "Default")
      (node (ref "U5") (pin "L2") (pinfunction "NC_L2_L2") (pintype "passive+no_connect"))
    )
    (net (code "125") (name "unconnected-(U5B-NC_L3-PadL3)") (class "Default")
      (node (ref "U5") (pin "L3") (pinfunction "NC_L3_L3") (pintype "passive+no_connect"))
    )
    (net (code "126") (name "unconnected-(U5B-NC_L12-PadL12)") (class "Default")
      (node (ref "U5") (pin "L12") (pinfunction "NC_L12_L12") (pintype "passive+no_connect"))
    )
    (net (code "127") (name "unconnected-(U5B-NC_L13-PadL13)") (class "Default")
      (node (ref "U5") (pin "L13") (pinfunction "NC_L13_L13") (pintype "passive+no_connect"))
    )
    (net (code "128") (name "unconnected-(U5B-NC_L14-PadL14)") (class "Default")
      (node (ref "U5") (pin "L14") (pinfunction "NC_L14_L14") (pintype "passive+no_connect"))
    )
    (net (code "129") (name "unconnected-(U5B-NC_M1-PadM1)") (class "Default")
      (node (ref "U5") (pin "M1") (pinfunction "NC_M1_M1") (pintype "passive+no_connect"))
    )
    (net (code "130") (name "unconnected-(U5B-NC_M2-PadM2)") (class "Default")
      (node (ref "U5") (pin "M2") (pinfunction "NC_M2_M2") (pintype "passive+no_connect"))
    )
    (net (code "131") (name "unconnected-(U5B-NC_M3-PadM3)") (class "Default")
      (node (ref "U5") (pin "M3") (pinfunction "NC_M3_M3") (pintype "passive+no_connect"))
    )
    (net (code "132") (name "unconnected-(U5B-NC_M7-PadM7)") (class "Default")
      (node (ref "U5") (pin "M7") (pinfunction "NC_M7_M7") (pintype "passive+no_connect"))
    )
    (net (code "133") (name "unconnected-(U5B-NC_M8-PadM8)") (class "Default")
      (node (ref "U5") (pin "M8") (pinfunction "NC_M8_M8") (pintype "passive+no_connect"))
    )
    (net (code "134") (name "unconnected-(U5B-NC_M9-PadM9)") (class "Default")
      (node (ref "U5") (pin "M9") (pinfunction "NC_M9_M9") (pintype "passive+no_connect"))
    )
    (net (code "135") (name "unconnected-(U5B-NC_M10-PadM10)") (class "Default")
      (node (ref "U5") (pin "M10") (pinfunction "NC_M10_M10") (pintype "passive+no_connect"))
    )
    (net (code "136") (name "unconnected-(U5B-NC_M11-PadM11)") (class "Default")
      (node (ref "U5") (pin "M11") (pinfunction "NC_M11_M11") (pintype "passive+no_connect"))
    )
    (net (code "137") (name "unconnected-(U5B-NC_M12-PadM12)") (class "Default")
      (node (ref "U5") (pin "M12") (pinfunction "NC_M12_M12") (pintype "passive+no_connect"))
    )
    (net (code "138") (name "unconnected-(U5B-NC_M13-PadM13)") (class "Default")
      (node (ref "U5") (pin "M13") (pinfunction "NC_M13_M13") (pintype "passive+no_connect"))
    )
    (net (code "139") (name "unconnected-(U5B-NC_M14-PadM14)") (class "Default")
      (node (ref "U5") (pin "M14") (pinfunction "NC_M14_M14") (pintype "passive+no_connect"))
    )
    (net (code "140") (name "unconnected-(U5B-NC_N1-PadN1)") (class "Default")
      (node (ref "U5") (pin "N1") (pinfunction "NC_N1_N1") (pintype "passive+no_connect"))
    )
    (net (code "141") (name "unconnected-(U5B-NC_N3-PadN3)") (class "Default")
      (node (ref "U5") (pin "N3") (pinfunction "NC_N3_N3") (pintype "passive+no_connect"))
    )
    (net (code "142") (name "unconnected-(U5B-NC_N6-PadN6)") (class "Default")
      (node (ref "U5") (pin "N6") (pinfunction "NC_N6_N6") (pintype "passive+no_connect"))
    )
    (net (code "143") (name "unconnected-(U5B-NC_N7-PadN7)") (class "Default")
      (node (ref "U5") (pin "N7") (pinfunction "NC_N7_N7") (pintype "passive+no_connect"))
    )
    (net (code "144") (name "unconnected-(U5B-NC_N8-PadN8)") (class "Default")
      (node (ref "U5") (pin "N8") (pinfunction "NC_N8_N8") (pintype "passive+no_connect"))
    )
    (net (code "145") (name "unconnected-(U5B-NC_N9-PadN9)") (class "Default")
      (node (ref "U5") (pin "N9") (pinfunction "NC_N9_N9") (pintype "passive+no_connect"))
    )
    (net (code "146") (name "unconnected-(U5B-NC_N10-PadN10)") (class "Default")
      (node (ref "U5") (pin "N10") (pinfunction "NC_N10_N10") (pintype "passive+no_connect"))
    )
    (net (code "147") (name "unconnected-(U5B-NC_N11-PadN11)") (class "Default")
      (node (ref "U5") (pin "N11") (pinfunction "NC_N11_N11") (pintype "passive+no_connect"))
    )
    (net (code "148") (name "unconnected-(U5B-NC_N12-PadN12)") (class "Default")
      (node (ref "U5") (pin "N12") (pinfunction "NC_N12_N12") (pintype "passive+no_connect"))
    )
    (net (code "149") (name "unconnected-(U5B-NC_N13-PadN13)") (class "Default")
      (node (ref "U5") (pin "N13") (pinfunction "NC_N13_N13") (pintype "passive+no_connect"))
    )
    (net (code "150") (name "unconnected-(U5B-NC_N14-PadN14)") (class "Default")
      (node (ref "U5") (pin "N14") (pinfunction "NC_N14_N14") (pintype "passive+no_connect"))
    )
    (net (code "151") (name "unconnected-(U5B-NC_P1-PadP1)") (class "Default")
      (node (ref "U5") (pin "P1") (pinfunction "NC_P1_P1") (pintype "passive+no_connect"))
    )
    (net (code "152") (name "unconnected-(U5B-NC_P2-PadP2)") (class "Default")
      (node (ref "U5") (pin "P2") (pinfunction "NC_P2_P2") (pintype "passive+no_connect"))
    )
    (net (code "153") (name "unconnected-(U5B-NC_P7-PadP7)") (class "Default")
      (node (ref "U5") (pin "P7") (pinfunction "NC_P7_P7") (pintype "passive+no_connect"))
    )
    (net (code "154") (name "unconnected-(U5B-NC_P8-PadP8)") (class "Default")
      (node (ref "U5") (pin "P8") (pinfunction "NC_P8_P8") (pintype "passive+no_connect"))
    )
    (net (code "155") (name "unconnected-(U5B-NC_P9-PadP9)") (class "Default")
      (node (ref "U5") (pin "P9") (pinfunction "NC_P9_P9") (pintype "passive+no_connect"))
    )
    (net (code "156") (name "unconnected-(U5B-NC_P10-PadP10)") (class "Default")
      (node (ref "U5") (pin "P10") (pinfunction "NC_P10_P10") (pintype "passive+no_connect"))
    )
    (net (code "157") (name "unconnected-(U5B-NC_P11-PadP11)") (class "Default")
      (node (ref "U5") (pin "P11") (pinfunction "NC_P11_P11") (pintype "passive+no_connect"))
    )
    (net (code "158") (name "unconnected-(U5B-NC_P12-PadP12)") (class "Default")
      (node (ref "U5") (pin "P12") (pinfunction "NC_P12_P12") (pintype "passive+no_connect"))
    )
    (net (code "159") (name "unconnected-(U5B-NC_P13-PadP13)") (class "Default")
      (node (ref "U5") (pin "P13") (pinfunction "NC_P13_P13") (pintype "passive+no_connect"))
    )
    (net (code "160") (name "unconnected-(U5B-NC_P14-PadP14)") (class "Default")
      (node (ref "U5") (pin "P14") (pinfunction "NC_P14_P14") (pintype "passive+no_connect"))
    )
    (net (code "161") (name "unconnected-(U5B-VSF1-PadE9)") (class "Default")
      (node (ref "U5") (pin "E9") (pinfunction "VSF1_E9") (pintype "passive+no_connect"))
    )
    (net (code "162") (name "unconnected-(U5B-VSF2-PadE10)") (class "Default")
      (node (ref "U5") (pin "E10") (pinfunction "VSF2_E10") (pintype "passive+no_connect"))
    )
    (net (code "163") (name "unconnected-(U5B-VSF3-PadF10)") (class "Default")
      (node (ref "U5") (pin "F10") (pinfunction "VSF3_F10") (pintype "passive+no_connect"))
    )
    (net (code "164") (name "unconnected-(U5B-VSF4-PadK10)") (class "Default")
      (node (ref "U5") (pin "K10") (pinfunction "VSF4_K10") (pintype "passive+no_connect"))
    )
  )
)
